# Boost_Drive.net
KiCad netlist of a schematic drawn in Altium Designer
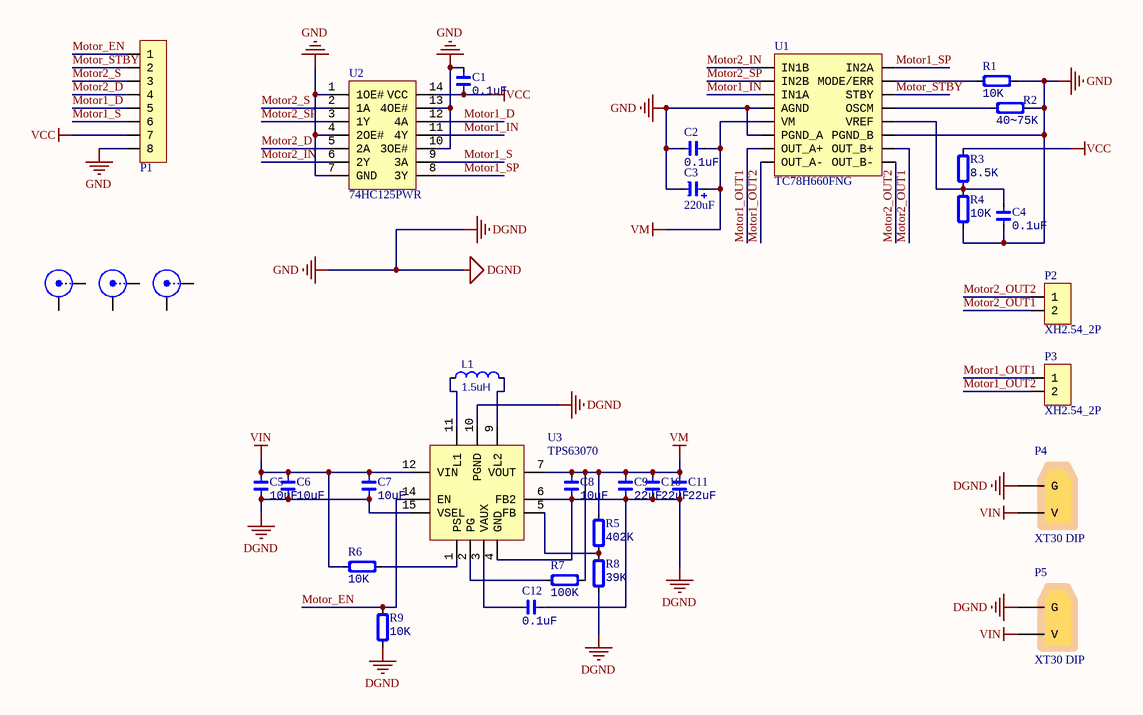
[diagram p0: Boost Drive.SchDoc]

(export (version "E")
  (design (tool "Eeschema 10.0.6"))
  (components
    (comp (ref "C1")
      (value "0.1uF")
      (footprint "0603_CAP")
      (description "Capacitor")
      (libsource (lib "Beacon") (part "0603_CAP"))
    )
    (comp (ref "C2")
      (value "0.1uF")
      (footprint "0603_CAP")
      (description "Capacitor")
      (libsource (lib "") (part "0603_CAP_1"))
    )
    (comp (ref "C3")
      (value "220uF")
      (footprint "CAP-TH_BD8.0-P3.50-D1.0-FD")
      (description "Electrolytic capacitor")
      (libsource (lib "Beacon") (part "CAP_8x11.5"))
    )
    (comp (ref "C4")
      (value "0.1uF")
      (footprint "0603_CAP")
      (description "Capacitor")
      (libsource (lib "Beacon") (part "0603_CAP"))
    )
    (comp (ref "C5")
      (value "10uF")
      (footprint "0805_CAP")
      (description "Capacitor")
      (libsource (lib "Beacon") (part "0805_CAP"))
    )
    (comp (ref "C6")
      (value "10uF")
      (footprint "0805_CAP")
      (description "Capacitor")
      (libsource (lib "Beacon") (part "0805_CAP"))
    )
    (comp (ref "C7")
      (value "10uF")
      (footprint "0603_CAP")
      (description "Capacitor")
      (libsource (lib "Beacon") (part "0603_CAP"))
    )
    (comp (ref "C8")
      (value "10uF")
      (footprint "0603_CAP")
      (description "Capacitor")
      (libsource (lib "Beacon") (part "0603_CAP"))
    )
    (comp (ref "C9")
      (value "22uF")
      (footprint "0805_CAP")
      (description "Capacitor")
      (libsource (lib "Beacon") (part "0805_CAP"))
    )
    (comp (ref "C10")
      (value "22uF")
      (footprint "0805_CAP")
      (description "Capacitor")
      (libsource (lib "Beacon") (part "0805_CAP"))
    )
    (comp (ref "C11")
      (value "22uF")
      (footprint "0805_CAP")
      (description "Capacitor")
      (libsource (lib "Beacon") (part "0805_CAP"))
    )
    (comp (ref "C12")
      (value "0.1uF")
      (footprint "0805_CAP")
      (description "Capacitor")
      (libsource (lib "") (part "0805_CAP_1"))
    )
    (comp (ref "Hole1") (value "Hole") (footprint "Hole") (libsource (lib "Beacon") (part "Hole")))
    (comp (ref "Hole2") (value "Hole") (footprint "Hole") (libsource (lib "Beacon") (part "Hole")))
    (comp (ref "Hole3") (value "Hole") (footprint "Hole") (libsource (lib "Beacon") (part "Hole")))
    (comp (ref "L1")
      (value "1.5uH")
      (footprint "CDRH74R")
      (description "Inductor")
      (fields
        (field (name "BOM_SUPPLIER PART") "C696490")
        (field (name "BOM_MANUFACTURER PART") "MPIT6045-330M-LF")
        (field (name "CONTRIBUTOR") "LCSC")
      )
      (libsource (lib "Beacon") (part "IND"))
    )
    (comp (ref "P1")
      (value "HDR1x8_2.54_F")
      (footprint "HDR_1X8_F")
      (description "Header")
      (libsource (lib "Beacon") (part "HDR1x8_2.54_F"))
    )
    (comp (ref "P2")
      (value "XH2.54_2P")
      (footprint "XH2.54_2P")
      (libsource (lib "Beacon") (part "XH2.54_2P"))
    )
    (comp (ref "P3")
      (value "XH2.54_2P")
      (footprint "XH2.54_2P")
      (libsource (lib "Beacon") (part "XH2.54_2P"))
    )
    (comp (ref "P4")
      (value "XT30 DIP")
      (footprint "XT30 DIP")
      (description "XT30 板载直头直插")
      (libsource (lib "Beacon") (part "XT30 DIP"))
    )
    (comp (ref "P5")
      (value "XT30 DIP")
      (footprint "XT30 DIP")
      (description "XT30 板载直头直插")
      (libsource (lib "Beacon") (part "XT30 DIP"))
    )
    (comp (ref "R1")
      (value "10K")
      (footprint "0805_RES")
      (description "Resistor")
      (libsource (lib "Beacon") (part "0805_RES"))
    )
    (comp (ref "R2")
      (value "40~75K")
      (footprint "0805_RES")
      (description "Resistor")
      (libsource (lib "Beacon") (part "0805_RES"))
    )
    (comp (ref "R3")
      (value "8.5K")
      (footprint "0805_RES")
      (description "Resistor")
      (libsource (lib "Beacon") (part "0805_RES"))
    )
    (comp (ref "R4")
      (value "10K")
      (footprint "0805_RES")
      (description "Resistor")
      (libsource (lib "Beacon") (part "0805_RES"))
    )
    (comp (ref "R5")
      (value "402K")
      (footprint "0805_RES")
      (description "Resistor")
      (libsource (lib "Beacon") (part "0805_RES"))
    )
    (comp (ref "R6")
      (value "10K")
      (footprint "0805_RES")
      (description "Resistor")
      (libsource (lib "Beacon") (part "0805_RES"))
    )
    (comp (ref "R7")
      (value "100K")
      (footprint "0805_RES")
      (description "Resistor")
      (libsource (lib "Beacon") (part "0805_RES"))
    )
    (comp (ref "R8")
      (value "39K")
      (footprint "0805_RES")
      (description "Resistor")
      (libsource (lib "Beacon") (part "0805_RES"))
    )
    (comp (ref "R9")
      (value "10K")
      (footprint "0805_RES")
      (description "Resistor")
      (libsource (lib "Beacon") (part "0805_RES"))
    )
    (comp (ref "U1")
      (value "TC78H660FNG")
      (footprint "TSSOP-16_L5.0-W4.4-P0.65-LS6.4-BL")
      (libsource (lib "Beacon") (part "TC78H660FNG"))
    )
    (comp (ref "U2")
      (value "74HC125PWR")
      (footprint "TSSOP-14_L5.0-W4.4-P0.65-LS6.5-BL")
      (libsource (lib "Beacon") (part "74HC125PWR"))
    )
    (comp (ref "U3")
      (value "TPS63070")
      (footprint "VQFN-15_L3.0-W2.5-P0.50-BL")
      (libsource (lib "Beacon") (part "TPS63070"))
    )
  )
  (nets
    (net (code "1") (name "/Motor1_D") (class "Default")
      (node (ref "P1") (pin "5") (pinfunction "5_5") (pintype "passive"))
      (node (ref "U2") (pin "12") (pinfunction "4A_12") (pintype "passive"))
    )
    (net (code "2") (name "/Motor1_IN") (class "Default")
      (node (ref "U1") (pin "3") (pinfunction "IN1A_3") (pintype "passive"))
      (node (ref "U2") (pin "11") (pinfunction "4Y_11") (pintype "passive"))
    )
    (net (code "3") (name "/Motor1_OUT1") (class "Default")
      (node (ref "P3") (pin "1") (pinfunction "1_1") (pintype "passive"))
      (node (ref "U1") (pin "7") (pinfunction "OUT_A+_7") (pintype "passive"))
    )
    (net (code "4") (name "/Motor1_OUT2") (class "Default")
      (node (ref "P3") (pin "2") (pinfunction "2_2") (pintype "passive"))
      (node (ref "U1") (pin "8") (pinfunction "OUT_A-_8") (pintype "passive"))
    )
    (net (code "5") (name "/Motor1_S") (class "Default")
      (node (ref "P1") (pin "6") (pinfunction "6_6") (pintype "passive"))
      (node (ref "U2") (pin "9") (pinfunction "3A_9") (pintype "passive"))
    )
    (net (code "6") (name "/Motor1_SP") (class "Default")
      (node (ref "U1") (pin "16") (pinfunction "IN2A_16") (pintype "passive"))
      (node (ref "U2") (pin "8") (pinfunction "3Y_8") (pintype "passive"))
    )
    (net (code "7") (name "/Motor2_D") (class "Default")
      (node (ref "P1") (pin "4") (pinfunction "4_4") (pintype "passive"))
      (node (ref "U2") (pin "5") (pinfunction "2A_5") (pintype "passive"))
    )
    (net (code "8") (name "/Motor2_IN") (class "Default")
      (node (ref "U1") (pin "1") (pinfunction "IN1B_1") (pintype "passive"))
      (node (ref "U2") (pin "6") (pinfunction "2Y_6") (pintype "passive"))
    )
    (net (code "9") (name "/Motor2_OUT1") (class "Default")
      (node (ref "P2") (pin "2") (pinfunction "2_2") (pintype "passive"))
      (node (ref "U1") (pin "10") (pinfunction "OUT_B+_10") (pintype "passive"))
    )
    (net (code "10") (name "/Motor2_OUT2") (class "Default")
      (node (ref "P2") (pin "1") (pinfunction "1_1") (pintype "passive"))
      (node (ref "U1") (pin "9") (pinfunction "OUT_B-_9") (pintype "passive"))
    )
    (net (code "11") (name "/Motor2_S") (class "Default")
      (node (ref "P1") (pin "3") (pinfunction "3_3") (pintype "passive"))
      (node (ref "U2") (pin "2") (pinfunction "1A_2") (pintype "passive"))
    )
    (net (code "12") (name "/Motor2_SP") (class "Default")
      (node (ref "U1") (pin "2") (pinfunction "IN2B_2") (pintype "passive"))
      (node (ref "U2") (pin "3") (pinfunction "1Y_3") (pintype "passive"))
    )
    (net (code "13") (name "/Motor_EN") (class "Default")
      (node (ref "P1") (pin "1") (pinfunction "1_1") (pintype "passive"))
      (node (ref "R9") (pin "2") (pinfunction "2_2") (pintype "passive"))
      (node (ref "U3") (pin "14") (pinfunction "EN_14") (pintype "passive"))
    )
    (net (code "14") (name "/Motor_STBY") (class "Default")
      (node (ref "P1") (pin "2") (pinfunction "2_2") (pintype "passive"))
      (node (ref "U1") (pin "14") (pinfunction "STBY_14") (pintype "passive"))
    )
    (net (code "15") (name "DGND") (class "Default")
      (node (ref "C1") (pin "2") (pinfunction "2_2") (pintype "passive"))
      (node (ref "C10") (pin "1") (pinfunction "1_1") (pintype "passive"))
      (node (ref "C11") (pin "1") (pinfunction "1_1") (pintype "passive"))
      (node (ref "C12") (pin "1") (pinfunction "1_1") (pintype "passive"))
      (node (ref "C2") (pin "1") (pinfunction "1_1") (pintype "passive"))
      (node (ref "C3") (pin "2") (pinfunction "2_2") (pintype "passive"))
      (node (ref "C4") (pin "1") (pinfunction "1_1") (pintype "passive"))
      (node (ref "C5") (pin "1") (pinfunction "1_1") (pintype "passive"))
      (node (ref "C6") (pin "1") (pinfunction "1_1") (pintype "passive"))
      (node (ref "C7") (pin "1") (pinfunction "1_1") (pintype "passive"))
      (node (ref "C8") (pin "1") (pinfunction "1_1") (pintype "passive"))
      (node (ref "C9") (pin "1") (pinfunction "1_1") (pintype "passive"))
      (node (ref "P1") (pin "8") (pinfunction "8_8") (pintype "passive"))
      (node (ref "P4") (pin "2") (pinfunction "G_2") (pintype "passive"))
      (node (ref "P5") (pin "2") (pinfunction "G_2") (pintype "passive"))
      (node (ref "R1") (pin "1") (pinfunction "1_1") (pintype "passive"))
      (node (ref "R2") (pin "1") (pinfunction "1_1") (pintype "passive"))
      (node (ref "R4") (pin "1") (pinfunction "1_1") (pintype "passive"))
      (node (ref "R8") (pin "1") (pinfunction "1_1") (pintype "passive"))
      (node (ref "R9") (pin "1") (pinfunction "1_1") (pintype "passive"))
      (node (ref "U1") (pin "11") (pinfunction "PGND_B_11") (pintype "passive"))
      (node (ref "U1") (pin "4") (pinfunction "AGND_4") (pintype "passive"))
      (node (ref "U1") (pin "6") (pinfunction "PGND_A_6") (pintype "passive"))
      (node (ref "U2") (pin "1") (pinfunction "1OE#_1") (pintype "passive"))
      (node (ref "U2") (pin "10") (pinfunction "3OE#_10") (pintype "passive"))
      (node (ref "U2") (pin "13") (pinfunction "4OE#_13") (pintype "passive"))
      (node (ref "U2") (pin "4") (pinfunction "2OE#_4") (pintype "passive"))
      (node (ref "U2") (pin "7") (pinfunction "GND_7") (pintype "passive"))
      (node (ref "U3") (pin "10") (pinfunction "PGND_10") (pintype "passive"))
      (node (ref "U3") (pin "15") (pinfunction "VSEL_15") (pintype "passive"))
      (node (ref "U3") (pin "4") (pinfunction "GND_4") (pintype "passive"))
      (node (ref "U3") (pin "6") (pinfunction "FB2_6") (pintype "passive"))
    )
    (net (code "16") (name "Net-(U1-MODE{slash}ERR)") (class "Default")
      (node (ref "R1") (pin "2") (pinfunction "2_2") (pintype "passive"))
      (node (ref "U1") (pin "15") (pinfunction "MODE/ERR_15") (pintype "passive"))
    )
    (net (code "17") (name "Net-(U1-OSCM)") (class "Default")
      (node (ref "R2") (pin "2") (pinfunction "2_2") (pintype "passive"))
      (node (ref "U1") (pin "13") (pinfunction "OSCM_13") (pintype "passive"))
    )
    (net (code "18") (name "Net-(U1-VREF)") (class "Default")
      (node (ref "C4") (pin "2") (pinfunction "2_2") (pintype "passive"))
      (node (ref "R3") (pin "1") (pinfunction "1_1") (pintype "passive"))
      (node (ref "R4") (pin "2") (pinfunction "2_2") (pintype "passive"))
      (node (ref "U1") (pin "12") (pinfunction "VREF_12") (pintype "passive"))
    )
    (net (code "19") (name "Net-(U3-FB)") (class "Default")
      (node (ref "R5") (pin "1") (pinfunction "1_1") (pintype "passive"))
      (node (ref "R8") (pin "2") (pinfunction "2_2") (pintype "passive"))
      (node (ref "U3") (pin "5") (pinfunction "FB_5") (pintype "passive"))
    )
    (net (code "20") (name "Net-(U3-L1)") (class "Default")
      (node (ref "L1") (pin "1") (pinfunction "1_1") (pintype "passive"))
      (node (ref "U3") (pin "11") (pinfunction "L1_11") (pintype "passive"))
    )
    (net (code "21") (name "Net-(U3-L2)") (class "Default")
      (node (ref "L1") (pin "2") (pinfunction "2_2") (pintype "passive"))
      (node (ref "U3") (pin "9") (pinfunction "L2_9") (pintype "passive"))
    )
    (net (code "22") (name "Net-(U3-PG)") (class "Default")
      (node (ref "R7") (pin "1") (pinfunction "1_1") (pintype "passive"))
      (node (ref "U3") (pin "2") (pinfunction "PG_2") (pintype "passive"))
    )
    (net (code "23") (name "Net-(U3-PS)") (class "Default")
      (node (ref "R6") (pin "2") (pinfunction "2_2") (pintype "passive"))
      (node (ref "U3") (pin "1") (pinfunction "PS_1") (pintype "passive"))
    )
    (net (code "24") (name "Net-(U3-VAUX)") (class "Default")
      (node (ref "C12") (pin "2") (pinfunction "2_2") (pintype "passive"))
      (node (ref "U3") (pin "3") (pinfunction "VAUX_3") (pintype "passive"))
    )
    (net (code "25") (name "VCC") (class "Default")
      (node (ref "C1") (pin "1") (pinfunction "1_1") (pintype "passive"))
      (node (ref "P1") (pin "7") (pinfunction "7_7") (pintype "passive"))
      (node (ref "R3") (pin "2") (pinfunction "2_2") (pintype "passive"))
      (node (ref "U2") (pin "14") (pinfunction "VCC_14") (pintype "passive"))
    )
    (net (code "26") (name "VIN") (class "Default")
      (node (ref "C5") (pin "2") (pinfunction "2_2") (pintype "passive"))
      (node (ref "C6") (pin "2") (pinfunction "2_2") (pintype "passive"))
      (node (ref "C7") (pin "2") (pinfunction "2_2") (pintype "passive"))
      (node (ref "P4") (pin "1") (pinfunction "V_1") (pintype "passive"))
      (node (ref "P5") (pin "1") (pinfunction "V_1") (pintype "passive"))
      (node (ref "R6") (pin "1") (pinfunction "1_1") (pintype "passive"))
      (node (ref "U3") (pin "12") (pinfunction "VIN_12") (pintype "passive"))
    )
    (net (code "27") (name "VM") (class "Default")
      (node (ref "C10") (pin "2") (pinfunction "2_2") (pintype "passive"))
      (node (ref "C11") (pin "2") (pinfunction "2_2") (pintype "passive"))
      (node (ref "C2") (pin "2") (pinfunction "2_2") (pintype "passive"))
      (node (ref "C3") (pin "1") (pinfunction "1_1") (pintype "passive"))
      (node (ref "C8") (pin "2") (pinfunction "2_2") (pintype "passive"))
      (node (ref "C9") (pin "2") (pinfunction "2_2") (pintype "passive"))
      (node (ref "R5") (pin "2") (pinfunction "2_2") (pintype "passive"))
      (node (ref "R7") (pin "2") (pinfunction "2_2") (pintype "passive"))
      (node (ref "U1") (pin "5") (pinfunction "VM_5") (pintype "passive"))
      (node (ref "U3") (pin "7") (pinfunction "VOUT_7") (pintype "passive"))
    )
    (net (code "28") (name "unconnected-(Hole1-X-Pad1)") (class "Default")
      (node (ref "Hole1") (pin "1") (pinfunction "X_1") (pintype "passive"))
    )
    (net (code "29") (name "unconnected-(Hole1-Y-Pad2)") (class "Default")
      (node (ref "Hole1") (pin "2") (pinfunction "Y_2") (pintype "passive"))
    )
    (net (code "30") (name "unconnected-(Hole2-X-Pad1)") (class "Default")
      (node (ref "Hole2") (pin "1") (pinfunction "X_1") (pintype "passive"))
    )
    (net (code "31") (name "unconnected-(Hole2-Y-Pad2)") (class "Default")
      (node (ref "Hole2") (pin "2") (pinfunction "Y_2") (pintype "passive"))
    )
    (net (code "32") (name "unconnected-(Hole3-X-Pad1)") (class "Default")
      (node (ref "Hole3") (pin "1") (pinfunction "X_1") (pintype "passive"))
    )
    (net (code "33") (name "unconnected-(Hole3-Y-Pad2)") (class "Default")
      (node (ref "Hole3") (pin "2") (pinfunction "Y_2") (pintype "passive"))
    )
  )
)
